# GPS.net
KiCad netlist of a schematic drawn in Altium Designer
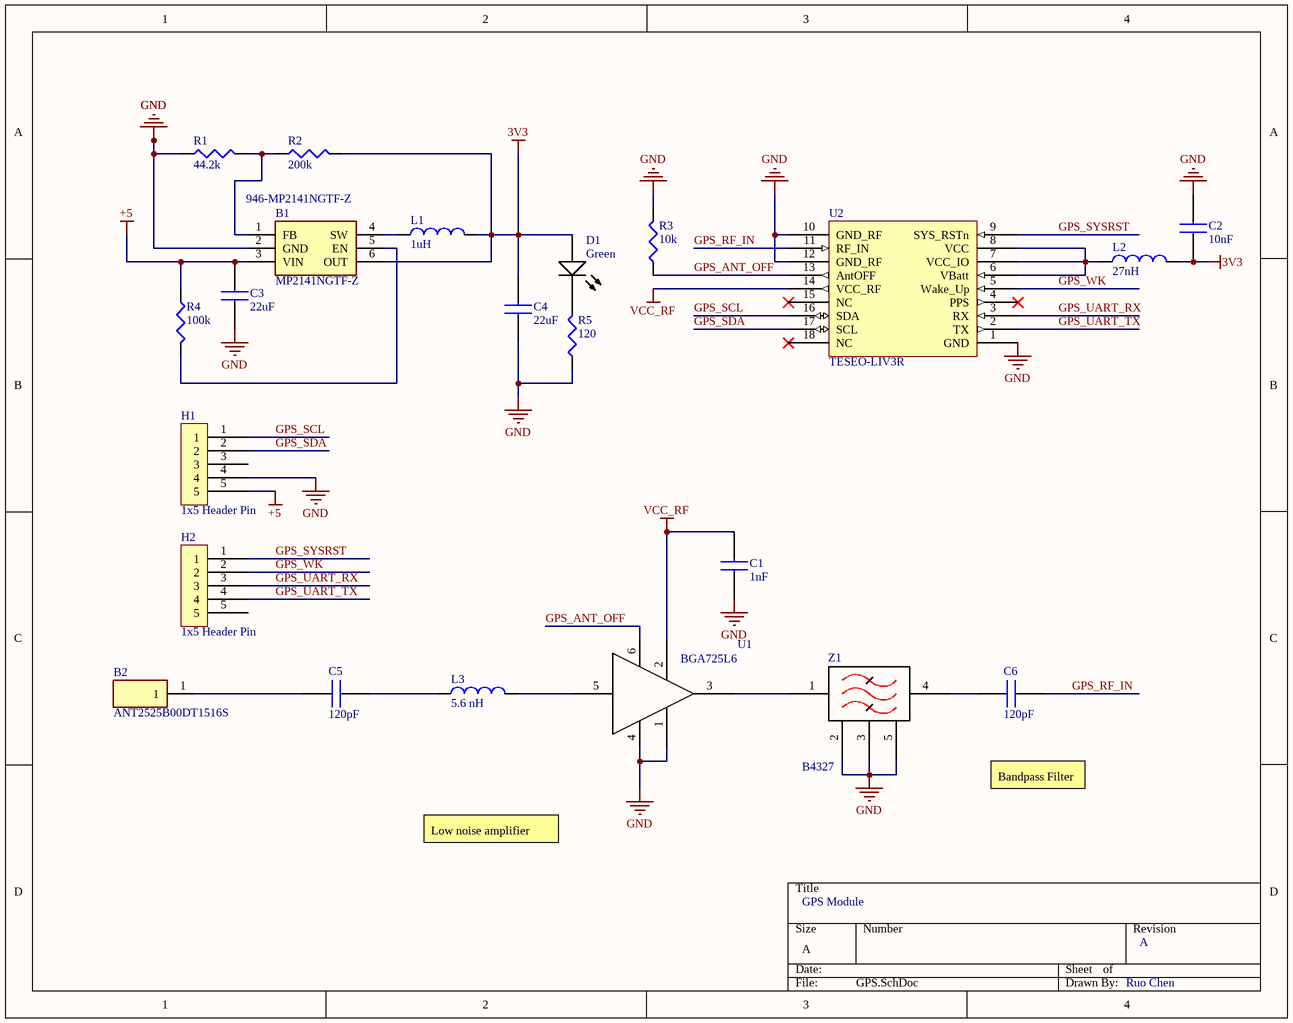
[diagram p0: GPS.SchDoc]

(export (version "E")
  (design (tool "Eeschema 10.0.6"))
  (components
    (comp (ref "B1")
      (value "MP2141NGTF-Z")
      (footprint "MP2141NGTF-Z")
      (description "IC REG 1A STEP-DOWN SYNCH 2.2MHz")
      (fields
        (field (name "MOUSER PART NUMBER") "946-MP2141NGTF-Z")
        (field (name "SUPPLIER PART NUMBER 1") "946-MP2141NGTF-Z")
      )
      (libsource (lib "Regulators") (part "MP2141NGTF-Z"))
    )
    (comp (ref "B2")
      (value "ANT2525B00DT1516S")
      (footprint "ANT2525B00DT1516S")
      (description "Antennas 20MHz 1575-1606MHz GPS & GLONASS")
      (fields (field (name "MOUSER PART NUMBER") "603-ANT225B00DT1516S"))
      (libsource (lib "Antennas") (part "ANT2525B00DT1516S"))
    )
    (comp (ref "C1")
      (value "1nF")
      (footprint "CAP_1005M(0402)")
      (description "Chip Capacitor, 1nF +/-10%, 50V, 0402, Thickness 0.5 mm")
      (fields (field (name "TOLERANCE") "+/-10%"))
      (libsource (lib "Capacitors") (part "GCM155R71H102KA37"))
    )
    (comp (ref "C2")
      (value "10nF")
      (footprint "CAP_1005M(0402)")
      (description "Chip Capacitor, 10nF +/-10%, 50V, 0402, Thickness 0.5 mm")
      (fields (field (name "TOLERANCE") "+/-10%"))
      (libsource (lib "Capacitors") (part "GCM155R71H103KA55D"))
    )
    (comp (ref "C3")
      (value "22uF")
      (footprint "CAP_3225M(1210)")
      (description "Chip Capacitor, 22uF +/-10%, 25V, 3225, Thickness 2.5 mm")
      (fields (field (name "TOLERANCE") "+/-10%"))
      (libsource (lib "Capacitors") (part "GCM32EC71E226KE36K"))
    )
    (comp (ref "C4")
      (value "22uF")
      (footprint "CAP_3225M(1210)")
      (description "Chip Capacitor, 22uF +/-10%, 25V, 3225, Thickness 2.5 mm")
      (fields (field (name "TOLERANCE") "+/-10%"))
      (libsource (lib "Capacitors") (part "GCM32EC71E226KE36K"))
    )
    (comp (ref "C5")
      (value "120pF")
      (footprint "CAP_1005M(0402)")
      (description "Chip Capacitor, 120pF +/-5%, 50V, 0402, Thickness 0.5 mm")
      (fields (field (name "TOLERANCE") "+/-5%"))
      (libsource (lib "Capacitors") (part "GCM1555C1H121JA16"))
    )
    (comp (ref "C6")
      (value "120pF")
      (footprint "CAP_1005M(0402)")
      (description "Chip Capacitor, 120pF +/-5%, 50V, 0402, Thickness 0.5 mm")
      (fields (field (name "TOLERANCE") "+/-5%"))
      (libsource (lib "Capacitors") (part "GCM1555C1H121JA16"))
    )
    (comp (ref "D1")
      (value "Green")
      (footprint "APG015CGKKC-TT")
      (description "Green LED")
      (libsource (lib "LED") (part "APG015CGKKC-TT"))
    )
    (comp (ref "H1")
      (value "1x5 Header Pin")
      (footprint "M22-2510505")
      (description "1x5, 3.5mm, 2 mm pitch")
      (libsource (lib "Headers") (part "M22-2510505"))
    )
    (comp (ref "H2")
      (value "1x5 Header Pin")
      (footprint "M22-2510505")
      (description "1x5, 3.5mm, 2 mm pitch")
      (libsource (lib "Headers") (part "M22-2510505"))
    )
    (comp (ref "L1")
      (value "1uH")
      (footprint "IND_1008(2520m)")
      (description "1uH, 20%, 1008(2520m), Inductor Shielded")
      (fields (field (name "TOLERANCE") "0.2 nH") (field (name "PART NUMBER") "L08055R6CEWTR"))
      (libsource (lib "Inductors") (part "1239AS-H-1R0M=P2"))
    )
    (comp (ref "L2")
      (value "27nH")
      (footprint "IND_0402(1005m)")
      (description "27nH, 5%, 0402(1005m), Inductor Unshielded, 350ma")
      (fields (field (name "TOLERANCE") "0.2 nH") (field (name "PART NUMBER") "L08055R6CEWTR"))
      (libsource (lib "Inductors") (part "LQG15HS27NJ02D"))
    )
    (comp (ref "L3")
      (value "5.6 nH")
      (footprint "IND_(0805)")
      (description "5.6(+/- 0.2) nH 0402 Inductor Unshielded")
      (fields (field (name "TOLERANCE") "0.2 nH") (field (name "PART NUMBER") "L08055R6CEWTR"))
      (libsource (lib "Inductors") (part "L08055R6CESTR"))
    )
    (comp (ref "R1")
      (value "44.2k")
      (footprint "RES_YAG_0402")
      (description "200k, 0402(1005m), 01(03m)h, 1%, 50V, -55-155 C, 1/16W")
      (libsource (lib "Resistors") (part "RT0402FRE07200KL"))
    )
    (comp (ref "R2")
      (value "200k")
      (footprint "RES_YAG_0402")
      (description "44.2k, 0402(1005m), 01(03m)h, 1%, 50V, -55-155 C, 1/16W")
      (libsource (lib "Resistors") (part "RT0402FRE0744K2L"))
    )
    (comp (ref "R3")
      (value "10k")
      (footprint "RES_YAG_0402")
      (description "10k, 0402(1005m), 01(03m)h, 1%, 50V, -55-155 C, 1/16W")
      (libsource (lib "Resistors") (part "RT0402FRE0710KL"))
    )
    (comp (ref "R4")
      (value "100k")
      (footprint "RES_YAG_0402")
      (description "100k, 0402(1005m), 01(03m)h, 1%, 50V, -55-155 C, 1/16W")
      (libsource (lib "Resistors") (part "RT0402FRE07100KL"))
    )
    (comp (ref "R5")
      (value "120")
      (footprint "RES_YAG_0402")
      (description "120, 0402(1005m), 01(03m)h, 1%, 50V, -55-155 C, 1/16W")
      (libsource (lib "Resistors") (part "RT0402FRE07120RL"))
    )
    (comp (ref "U1")
      (value "BGA725L6")
      (footprint "BGA725L6E6327FTSA1")
      (description "RF Amplifier RF SILICON MMIC 1.55 GHz to 1.615 GHz 1.5 V to 3.6 V 3.6 mA 20 dB")
      (libsource (lib "LNA") (part "BGA725L6"))
    )
    (comp (ref "U2")
      (value "TESEO-LIV3R")
      (footprint "TESEOLIV3R")
      (description "GNSS / GPS Modules Teseo ROM GNSS module")
      (libsource (lib "IC") (part "TESEO-LIV3R"))
    )
    (comp (ref "Z1")
      (value "B4327")
      (footprint "B39162B4327P810")
      (libsource (lib "Filters") (part "B39162B4327P810"))
    )
  )
  (nets
    (net (code "1") (name "+5") (class "Default")
      (node (ref "B1") (pin "3") (pinfunction "VIN_3") (pintype "passive"))
      (node (ref "C3") (pin "1") (pinfunction "1_1") (pintype "passive"))
      (node (ref "H1") (pin "5") (pinfunction "5_5") (pintype "passive"))
      (node (ref "R4") (pin "1") (pinfunction "1_1") (pintype "passive"))
    )
    (net (code "2") (name "/GPS_ANT_OFF") (class "Default")
      (node (ref "R3") (pin "1") (pinfunction "1_1") (pintype "passive"))
      (node (ref "U1") (pin "6") (pinfunction "6_6") (pintype "passive"))
      (node (ref "U2") (pin "13") (pinfunction "AntOFF_13") (pintype "output"))
    )
    (net (code "3") (name "/GPS_RF_IN") (class "Default")
      (node (ref "C6") (pin "1") (pinfunction "1_1") (pintype "passive"))
      (node (ref "U2") (pin "11") (pinfunction "RF_IN_11") (pintype "input"))
    )
    (net (code "4") (name "/GPS_SCL") (class "Default")
      (node (ref "H1") (pin "1") (pinfunction "1_1") (pintype "passive"))
      (node (ref "U2") (pin "16") (pinfunction "SDA_16") (pintype "bidirectional"))
    )
    (net (code "5") (name "/GPS_SDA") (class "Default")
      (node (ref "H1") (pin "2") (pinfunction "2_2") (pintype "passive"))
      (node (ref "U2") (pin "17") (pinfunction "SCL_17") (pintype "bidirectional"))
    )
    (net (code "6") (name "/GPS_SYSRST") (class "Default")
      (node (ref "H2") (pin "1") (pinfunction "1_1") (pintype "passive"))
      (node (ref "U2") (pin "9") (pinfunction "SYS_RSTn_9") (pintype "input"))
    )
    (net (code "7") (name "/GPS_UART_RX") (class "Default")
      (node (ref "H2") (pin "3") (pinfunction "3_3") (pintype "passive"))
      (node (ref "U2") (pin "3") (pinfunction "RX_3") (pintype "input"))
    )
    (net (code "8") (name "/GPS_UART_TX") (class "Default")
      (node (ref "H2") (pin "4") (pinfunction "4_4") (pintype "passive"))
      (node (ref "U2") (pin "2") (pinfunction "TX_2") (pintype "output"))
    )
    (net (code "9") (name "/GPS_WK") (class "Default")
      (node (ref "H2") (pin "2") (pinfunction "2_2") (pintype "passive"))
      (node (ref "U2") (pin "5") (pinfunction "Wake_Up_5") (pintype "input"))
    )
    (net (code "10") (name "3V3") (class "Default")
      (node (ref "B1") (pin "6") (pinfunction "OUT_6") (pintype "passive"))
      (node (ref "C2") (pin "2") (pinfunction "2_2") (pintype "passive"))
      (node (ref "C4") (pin "1") (pinfunction "1_1") (pintype "passive"))
      (node (ref "D1") (pin "2") (pinfunction "A_2") (pintype "passive"))
      (node (ref "L1") (pin "2") (pinfunction "2_2") (pintype "passive"))
      (node (ref "L2") (pin "2") (pinfunction "2_2") (pintype "passive"))
      (node (ref "R2") (pin "2") (pinfunction "2_2") (pintype "passive"))
    )
    (net (code "11") (name "GND") (class "Default")
      (node (ref "B1") (pin "2") (pinfunction "GND_2") (pintype "passive"))
      (node (ref "C1") (pin "2") (pinfunction "2_2") (pintype "passive"))
      (node (ref "C2") (pin "1") (pinfunction "1_1") (pintype "passive"))
      (node (ref "C3") (pin "2") (pinfunction "2_2") (pintype "passive"))
      (node (ref "C4") (pin "2") (pinfunction "2_2") (pintype "passive"))
      (node (ref "H1") (pin "4") (pinfunction "4_4") (pintype "passive"))
      (node (ref "R1") (pin "1") (pinfunction "1_1") (pintype "passive"))
      (node (ref "R3") (pin "2") (pinfunction "2_2") (pintype "passive"))
      (node (ref "R5") (pin "1") (pinfunction "1_1") (pintype "passive"))
      (node (ref "U1") (pin "1") (pinfunction "1_1") (pintype "passive"))
      (node (ref "U1") (pin "4") (pinfunction "4_4") (pintype "passive"))
      (node (ref "U2") (pin "1") (pinfunction "GND_1") (pintype "power_in"))
      (node (ref "U2") (pin "10") (pinfunction "GND_RF_10") (pintype "power_in"))
      (node (ref "U2") (pin "12") (pinfunction "GND_RF_12") (pintype "power_in"))
      (node (ref "Z1") (pin "2") (pinfunction "2_2") (pintype "passive"))
      (node (ref "Z1") (pin "3") (pinfunction "3_3") (pintype "passive"))
      (node (ref "Z1") (pin "5") (pinfunction "5_5") (pintype "passive"))
    )
    (net (code "12") (name "Net-(B1-EN)") (class "Default")
      (node (ref "B1") (pin "5") (pinfunction "EN_5") (pintype "passive"))
      (node (ref "R4") (pin "2") (pinfunction "2_2") (pintype "passive"))
    )
    (net (code "13") (name "Net-(B1-FB)") (class "Default")
      (node (ref "B1") (pin "1") (pinfunction "FB_1") (pintype "passive"))
      (node (ref "R1") (pin "2") (pinfunction "2_2") (pintype "passive"))
      (node (ref "R2") (pin "1") (pinfunction "1_1") (pintype "passive"))
    )
    (net (code "14") (name "Net-(B1-SW)") (class "Default")
      (node (ref "B1") (pin "4") (pinfunction "SW_4") (pintype "passive"))
      (node (ref "L1") (pin "1") (pinfunction "1_1") (pintype "passive"))
    )
    (net (code "15") (name "Net-(B2-Pad1)") (class "Default")
      (node (ref "B2") (pin "1") (pinfunction "1_1") (pintype "passive"))
      (node (ref "C5") (pin "2") (pinfunction "2_2") (pintype "passive"))
    )
    (net (code "16") (name "Net-(C5-Pad1)") (class "Default")
      (node (ref "C5") (pin "1") (pinfunction "1_1") (pintype "passive"))
      (node (ref "L3") (pin "1") (pinfunction "1_1") (pintype "passive"))
    )
    (net (code "17") (name "Net-(C6-Pad2)") (class "Default")
      (node (ref "C6") (pin "2") (pinfunction "2_2") (pintype "passive"))
      (node (ref "Z1") (pin "4") (pinfunction "4_4") (pintype "passive"))
    )
    (net (code "18") (name "Net-(D1-K)") (class "Default")
      (node (ref "D1") (pin "1") (pinfunction "K_1") (pintype "passive"))
      (node (ref "R5") (pin "2") (pinfunction "2_2") (pintype "passive"))
    )
    (net (code "19") (name "Net-(L3-Pad2)") (class "Default")
      (node (ref "L3") (pin "2") (pinfunction "2_2") (pintype "passive"))
      (node (ref "U1") (pin "5") (pinfunction "5_5") (pintype "passive"))
    )
    (net (code "20") (name "Net-(U1-Pad3)") (class "Default")
      (node (ref "U1") (pin "3") (pinfunction "3_3") (pintype "passive"))
      (node (ref "Z1") (pin "1") (pinfunction "1_1") (pintype "passive"))
    )
    (net (code "21") (name "Net-(U2-VBatt)") (class "Default")
      (node (ref "L2") (pin "1") (pinfunction "1_1") (pintype "passive"))
      (node (ref "U2") (pin "6") (pinfunction "VBatt_6") (pintype "input"))
      (node (ref "U2") (pin "7") (pinfunction "VCC_IO_7") (pintype "power_in"))
      (node (ref "U2") (pin "8") (pinfunction "VCC_8") (pintype "power_in"))
    )
    (net (code "22") (name "VCC_RF") (class "Default")
      (node (ref "C1") (pin "1") (pinfunction "1_1") (pintype "passive"))
      (node (ref "U1") (pin "2") (pinfunction "2_2") (pintype "passive"))
      (node (ref "U2") (pin "14") (pinfunction "VCC_RF_14") (pintype "output"))
    )
    (net (code "23") (name "unconnected-(H1-Pad3)") (class "Default")
      (node (ref "H1") (pin "3") (pinfunction "3_3") (pintype "passive"))
    )
    (net (code "24") (name "unconnected-(H2-Pad5)") (class "Default")
      (node (ref "H2") (pin "5") (pinfunction "5_5") (pintype "passive"))
    )
    (net (code "25") (name "unconnected-(U2-NC-Pad15)") (class "Default")
      (node (ref "U2") (pin "15") (pinfunction "NC_15") (pintype "passive+no_connect"))
    )
    (net (code "26") (name "unconnected-(U2-NC-Pad18)") (class "Default")
      (node (ref "U2") (pin "18") (pinfunction "NC_18") (pintype "passive+no_connect"))
    )
    (net (code "27") (name "unconnected-(U2-PPS-Pad4)") (class "Default")
      (node (ref "U2") (pin "4") (pinfunction "PPS_4") (pintype "output+no_connect"))
    )
  )
)
